# Board.net
KiCad netlist of a schematic drawn in EAGLE
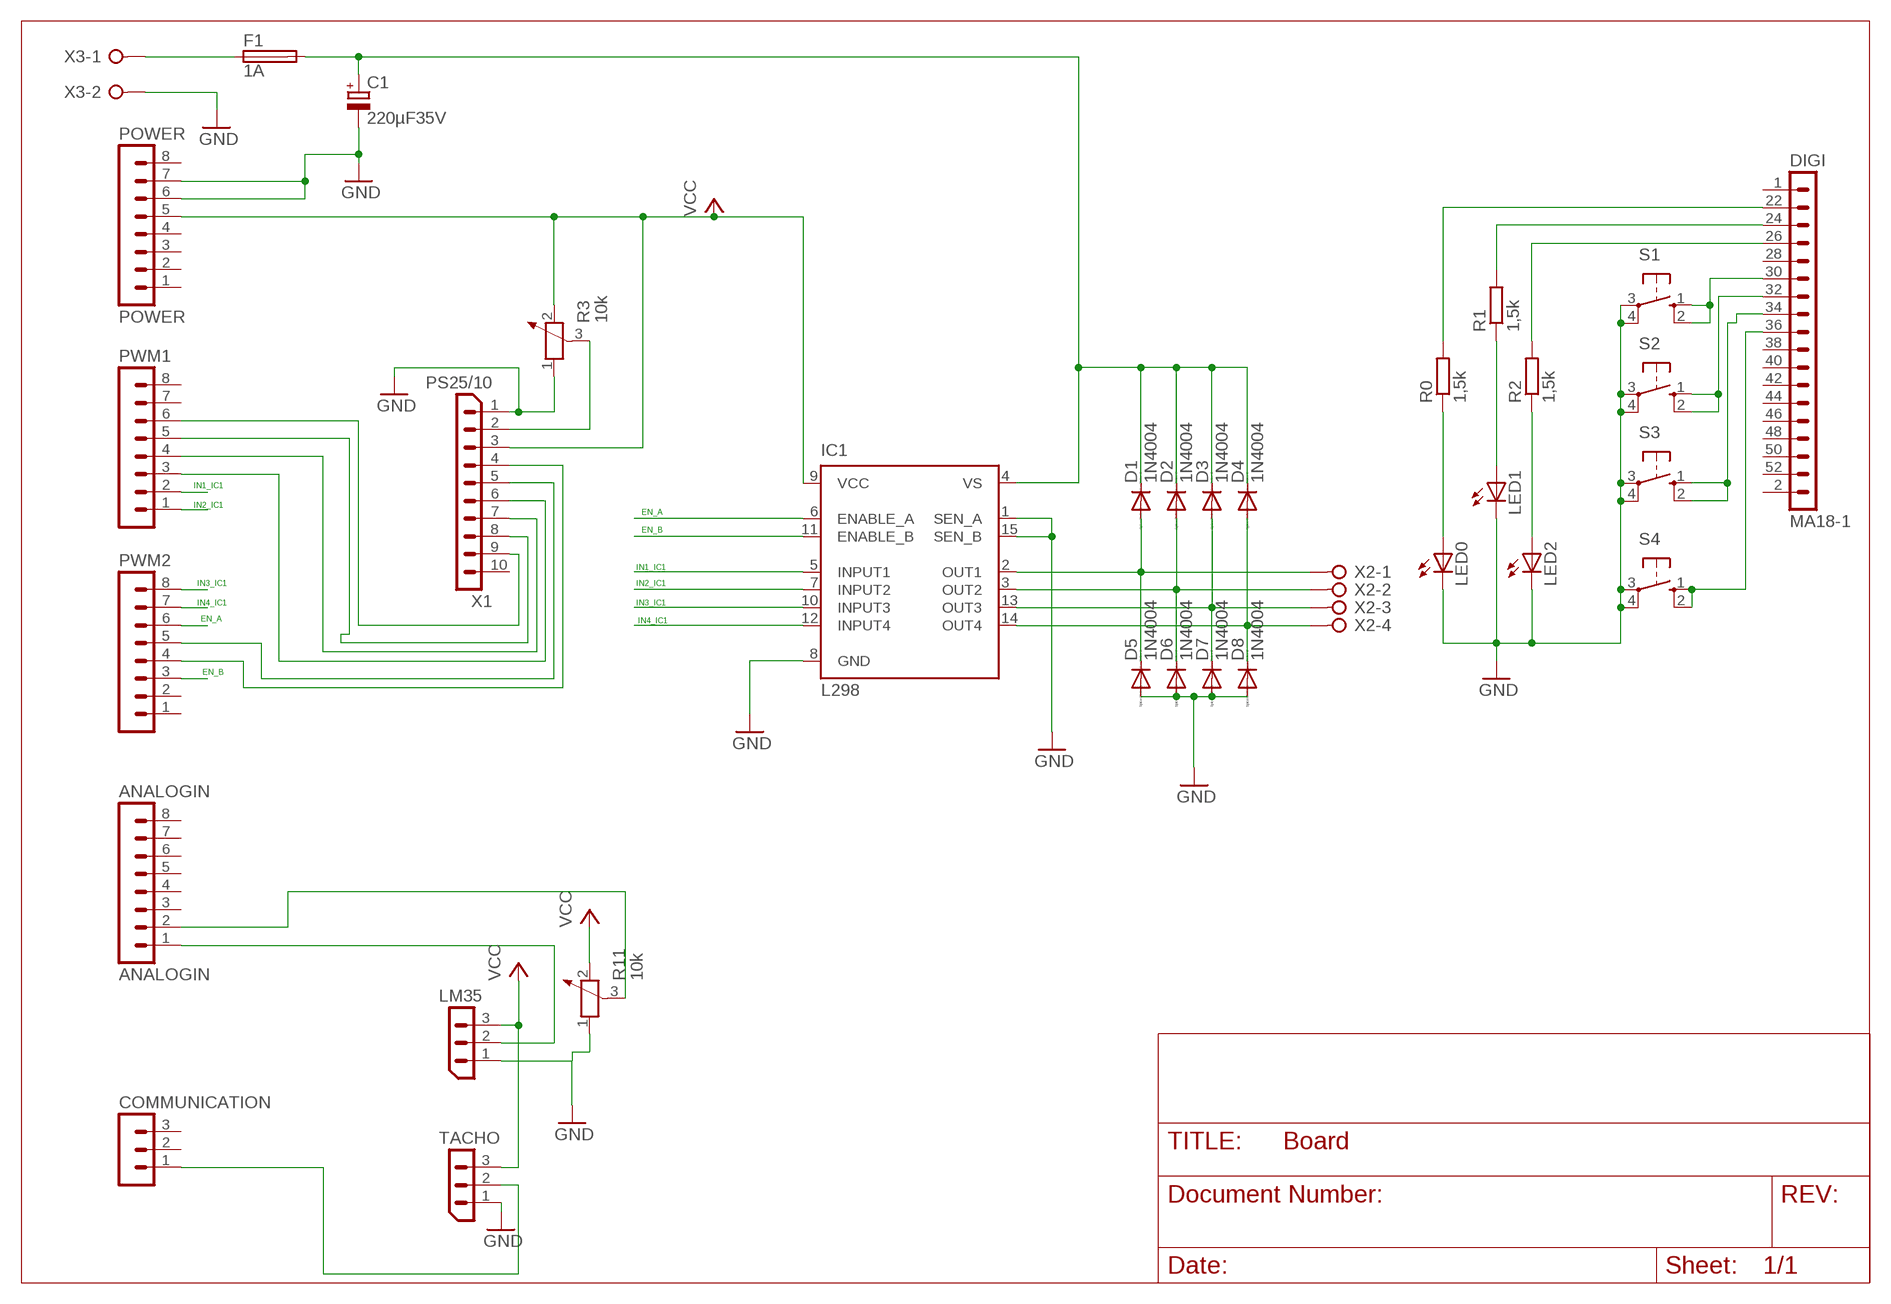
[diagram p0: schematic, sheet 1]

(export (version "E")
  (design (tool "Eeschema 10.0.6"))
  (components
    (comp (ref "ANALOGIN")
      (value "ANALOGIN")
      (footprint "eagle-import:MA08-1")
      (libsource (lib "eagle-import") (part "MA08-1"))
    )
    (comp (ref "C1")
      (value "220µF35V")
      (footprint "eagle-import:E5-10,5")
      (libsource (lib "eagle-import") (part "CPOL-EUE5-10.5"))
    )
    (comp (ref "COMMUNICATION")
      (value "MA03-1")
      (footprint "eagle-import:MA03-1")
      (libsource (lib "eagle-import") (part "MA03-1"))
    )
    (comp (ref "D1")
      (value "1N4004")
      (footprint "eagle-import:DO41-10")
      (libsource (lib "eagle-import") (part "1N4004"))
    )
    (comp (ref "D2")
      (value "1N4004")
      (footprint "eagle-import:DO41-10")
      (libsource (lib "eagle-import") (part "1N4004"))
    )
    (comp (ref "D3")
      (value "1N4004")
      (footprint "eagle-import:DO41-10")
      (libsource (lib "eagle-import") (part "1N4004"))
    )
    (comp (ref "D4")
      (value "1N4004")
      (footprint "eagle-import:DO41-10")
      (libsource (lib "eagle-import") (part "1N4004"))
    )
    (comp (ref "D5")
      (value "1N4004")
      (footprint "eagle-import:DO41-10")
      (libsource (lib "eagle-import") (part "1N4004"))
    )
    (comp (ref "D6")
      (value "1N4004")
      (footprint "eagle-import:DO41-10")
      (libsource (lib "eagle-import") (part "1N4004"))
    )
    (comp (ref "D7")
      (value "1N4004")
      (footprint "eagle-import:DO41-10")
      (libsource (lib "eagle-import") (part "1N4004"))
    )
    (comp (ref "D8")
      (value "1N4004")
      (footprint "eagle-import:DO41-10")
      (libsource (lib "eagle-import") (part "1N4004"))
    )
    (comp (ref "DIGI")
      (value "MA18-1")
      (footprint "eagle-import:MA18-1")
      (libsource (lib "eagle-import") (part "MA18-1"))
    )
    (comp (ref "F1")
      (value "1A")
      (footprint "eagle-import:19560")
      (fields (field (name "MPN") "56000001009"))
      (libsource (lib "eagle-import") (part "19560"))
    )
    (comp (ref "IC1")
      (value "L298")
      (footprint "eagle-import:MULTIWATT-15")
      (fields (field (name "MPN") "L298N"))
      (libsource (lib "eagle-import") (part "L298"))
    )
    (comp (ref "LED0")
      (value "LED3MM")
      (footprint "eagle-import:LED3MM")
      (libsource (lib "eagle-import") (part "LED3MM"))
    )
    (comp (ref "LED1")
      (value "LED3MM")
      (footprint "eagle-import:LED3MM")
      (libsource (lib "eagle-import") (part "LED3MM"))
    )
    (comp (ref "LED2")
      (value "LED3MM")
      (footprint "eagle-import:LED3MM")
      (libsource (lib "eagle-import") (part "LED3MM"))
    )
    (comp (ref "LM35")
      (value "PS25/10")
      (footprint "eagle-import:PS25_10")
      (libsource (lib "eagle-import") (part "Platinenstecker_3pol_PS25/10"))
    )
    (comp (ref "POWER")
      (value "POWER")
      (footprint "eagle-import:MA08-1")
      (libsource (lib "eagle-import") (part "MA08-1"))
    )
    (comp (ref "PWM1")
      (value "MA08-1")
      (footprint "eagle-import:MA08-1")
      (libsource (lib "eagle-import") (part "MA08-1"))
    )
    (comp (ref "PWM2")
      (value "MA08-1")
      (footprint "eagle-import:MA08-1")
      (libsource (lib "eagle-import") (part "MA08-1"))
    )
    (comp (ref "R0")
      (value "1,5k")
      (footprint "eagle-import:0207_10")
      (libsource (lib "eagle-import") (part "R-EU_0207/10"))
    )
    (comp (ref "R1")
      (value "1,5k")
      (footprint "eagle-import:0207_10")
      (libsource (lib "eagle-import") (part "R-EU_0207/10"))
    )
    (comp (ref "R2")
      (value "1,5k")
      (footprint "eagle-import:0207_10")
      (libsource (lib "eagle-import") (part "R-EU_0207/10"))
    )
    (comp (ref "R3")
      (value "10k")
      (footprint "eagle-import:PT-10")
      (libsource (lib "eagle-import") (part "POTENTIOMETER_PT-10"))
    )
    (comp (ref "R11")
      (value "10k")
      (footprint "eagle-import:PT-10")
      (libsource (lib "eagle-import") (part "POTENTIOMETER_PT-10"))
    )
    (comp (ref "S1")
      (value "10-XX")
      (footprint "eagle-import:B3F-10XX")
      (fields (field (name "MPN") "B3F-1000"))
      (libsource (lib "eagle-import") (part "10-XX"))
    )
    (comp (ref "S2")
      (value "10-XX")
      (footprint "eagle-import:B3F-10XX")
      (fields (field (name "MPN") "B3F-1000"))
      (libsource (lib "eagle-import") (part "10-XX"))
    )
    (comp (ref "S3")
      (value "10-XX")
      (footprint "eagle-import:B3F-10XX")
      (fields (field (name "MPN") "B3F-1000"))
      (libsource (lib "eagle-import") (part "10-XX"))
    )
    (comp (ref "S4")
      (value "10-XX")
      (footprint "eagle-import:B3F-10XX")
      (fields (field (name "MPN") "B3F-1000"))
      (libsource (lib "eagle-import") (part "10-XX"))
    )
    (comp (ref "TACHO")
      (value "PS25/10")
      (footprint "eagle-import:PS25_10")
      (libsource (lib "eagle-import") (part "Platinenstecker_3pol_PS25/10"))
    )
    (comp (ref "X1")
      (value "PS25/10")
      (footprint "eagle-import:PS25_10")
      (libsource (lib "eagle-import") (part "PS25/10"))
    )
    (comp (ref "X2")
      (value "W237-04P")
      (footprint "eagle-import:W237-4P")
      (libsource (lib "eagle-import") (part "W237-04P"))
    )
    (comp (ref "X3")
      (value "W237-02P")
      (footprint "eagle-import:W237-132")
      (libsource (lib "eagle-import") (part "W237-02P"))
    )
  )
  (nets
    (net (code "1") (name "/EN_A") (class "Default")
      (node (ref "IC1") (pin "6") (pinfunction "ENABLE_A_6") (pintype "input"))
      (node (ref "PWM2") (pin "6") (pinfunction "6_6") (pintype "passive"))
    )
    (net (code "2") (name "/EN_B") (class "Default")
      (node (ref "IC1") (pin "11") (pinfunction "ENABLE_B_11") (pintype "input"))
      (node (ref "PWM2") (pin "3") (pinfunction "3_3") (pintype "passive"))
    )
    (net (code "3") (name "/IN1_IC1") (class "Default")
      (node (ref "IC1") (pin "5") (pinfunction "INPUT1_5") (pintype "input"))
      (node (ref "PWM1") (pin "2") (pinfunction "2_2") (pintype "passive"))
    )
    (net (code "4") (name "/IN2_IC1") (class "Default")
      (node (ref "IC1") (pin "7") (pinfunction "INPUT2_7") (pintype "input"))
      (node (ref "PWM1") (pin "1") (pinfunction "1_1") (pintype "passive"))
    )
    (net (code "5") (name "/IN3_IC1") (class "Default")
      (node (ref "IC1") (pin "10") (pinfunction "INPUT3_10") (pintype "input"))
      (node (ref "PWM2") (pin "8") (pinfunction "8_8") (pintype "passive"))
    )
    (net (code "6") (name "/IN4_IC1") (class "Default")
      (node (ref "IC1") (pin "12") (pinfunction "INPUT4_12") (pintype "input"))
      (node (ref "PWM2") (pin "7") (pinfunction "7_7") (pintype "passive"))
    )
    (net (code "7") (name "GND") (class "Default")
      (node (ref "C1") (pin "-") (pinfunction "-_-") (pintype "passive"))
      (node (ref "D5") (pin "A") (pinfunction "A_A") (pintype "passive"))
      (node (ref "D6") (pin "A") (pinfunction "A_A") (pintype "passive"))
      (node (ref "D7") (pin "A") (pinfunction "A_A") (pintype "passive"))
      (node (ref "D8") (pin "A") (pinfunction "A_A") (pintype "passive"))
      (node (ref "IC1") (pin "1") (pinfunction "SEN_A_1") (pintype "input"))
      (node (ref "IC1") (pin "15") (pinfunction "SEN_B_15") (pintype "input"))
      (node (ref "IC1") (pin "8") (pinfunction "GND_8") (pintype "power_in"))
      (node (ref "LED0") (pin "K") (pinfunction "C_K") (pintype "passive"))
      (node (ref "LED1") (pin "K") (pinfunction "C_K") (pintype "passive"))
      (node (ref "LED2") (pin "K") (pinfunction "C_K") (pintype "passive"))
      (node (ref "LM35") (pin "1") (pinfunction "1_1") (pintype "passive"))
      (node (ref "POWER") (pin "6") (pinfunction "6_6") (pintype "passive"))
      (node (ref "POWER") (pin "7") (pinfunction "7_7") (pintype "passive"))
      (node (ref "R11") (pin "1") (pinfunction "1_1") (pintype "passive"))
      (node (ref "R3") (pin "1") (pinfunction "1_1") (pintype "passive"))
      (node (ref "S1") (pin "3") (pinfunction "P_3") (pintype "passive"))
      (node (ref "S1") (pin "4") (pinfunction "P1_4") (pintype "passive"))
      (node (ref "S2") (pin "3") (pinfunction "P_3") (pintype "passive"))
      (node (ref "S2") (pin "4") (pinfunction "P1_4") (pintype "passive"))
      (node (ref "S3") (pin "3") (pinfunction "P_3") (pintype "passive"))
      (node (ref "S3") (pin "4") (pinfunction "P1_4") (pintype "passive"))
      (node (ref "S4") (pin "3") (pinfunction "P_3") (pintype "passive"))
      (node (ref "S4") (pin "4") (pinfunction "P1_4") (pintype "passive"))
      (node (ref "TACHO") (pin "1") (pinfunction "1_1") (pintype "passive"))
      (node (ref "X1") (pin "1") (pinfunction "1_1") (pintype "passive"))
      (node (ref "X3") (pin "2") (pinfunction "KL_2") (pintype "passive"))
    )
    (net (code "8") (name "Net-(ANALOGIN-Pad1)") (class "Default")
      (node (ref "ANALOGIN") (pin "1") (pinfunction "1_1") (pintype "passive"))
      (node (ref "LM35") (pin "2") (pinfunction "2_2") (pintype "passive"))
    )
    (net (code "9") (name "Net-(ANALOGIN-Pad2)") (class "Default")
      (node (ref "ANALOGIN") (pin "2") (pinfunction "2_2") (pintype "passive"))
      (node (ref "R11") (pin "3") (pinfunction "3_3") (pintype "passive"))
    )
    (net (code "10") (name "Net-(COMMUNICATION-Pad1)") (class "Default")
      (node (ref "COMMUNICATION") (pin "1") (pinfunction "1_1") (pintype "passive"))
      (node (ref "TACHO") (pin "2") (pinfunction "2_2") (pintype "passive"))
    )
    (net (code "11") (name "Net-(DIGI-Pad22)") (class "Default")
      (node (ref "DIGI") (pin "22") (pinfunction "22_22") (pintype "passive"))
      (node (ref "R0") (pin "2") (pinfunction "2_2") (pintype "passive"))
    )
    (net (code "12") (name "Net-(DIGI-Pad24)") (class "Default")
      (node (ref "DIGI") (pin "24") (pinfunction "24_24") (pintype "passive"))
      (node (ref "R1") (pin "2") (pinfunction "2_2") (pintype "passive"))
    )
    (net (code "13") (name "Net-(DIGI-Pad26)") (class "Default")
      (node (ref "DIGI") (pin "26") (pinfunction "26_26") (pintype "passive"))
      (node (ref "R2") (pin "2") (pinfunction "2_2") (pintype "passive"))
    )
    (net (code "14") (name "Net-(IC1-OUT1)") (class "Default")
      (node (ref "D1") (pin "A") (pinfunction "A_A") (pintype "passive"))
      (node (ref "D5") (pin "C") (pinfunction "C_C") (pintype "passive"))
      (node (ref "IC1") (pin "2") (pinfunction "OUT1_2") (pintype "output"))
      (node (ref "X2") (pin "1") (pinfunction "KL_1") (pintype "passive"))
    )
    (net (code "15") (name "Net-(IC1-OUT2)") (class "Default")
      (node (ref "D2") (pin "A") (pinfunction "A_A") (pintype "passive"))
      (node (ref "D6") (pin "C") (pinfunction "C_C") (pintype "passive"))
      (node (ref "IC1") (pin "3") (pinfunction "OUT2_3") (pintype "output"))
      (node (ref "X2") (pin "2") (pinfunction "KL_2") (pintype "passive"))
    )
    (net (code "16") (name "Net-(IC1-OUT3)") (class "Default")
      (node (ref "D3") (pin "A") (pinfunction "A_A") (pintype "passive"))
      (node (ref "D7") (pin "C") (pinfunction "C_C") (pintype "passive"))
      (node (ref "IC1") (pin "13") (pinfunction "OUT3_13") (pintype "output"))
      (node (ref "X2") (pin "3") (pinfunction "KL_3") (pintype "passive"))
    )
    (net (code "17") (name "Net-(IC1-OUT4)") (class "Default")
      (node (ref "D4") (pin "A") (pinfunction "A_A") (pintype "passive"))
      (node (ref "D8") (pin "C") (pinfunction "C_C") (pintype "passive"))
      (node (ref "IC1") (pin "14") (pinfunction "OUT4_14") (pintype "output"))
      (node (ref "X2") (pin "4") (pinfunction "KL_4") (pintype "passive"))
    )
    (net (code "18") (name "Net-(IC1-VS)") (class "Default")
      (node (ref "C1") (pin "+") (pinfunction "+_+") (pintype "passive"))
      (node (ref "D1") (pin "C") (pinfunction "C_C") (pintype "passive"))
      (node (ref "D2") (pin "C") (pinfunction "C_C") (pintype "passive"))
      (node (ref "D3") (pin "C") (pinfunction "C_C") (pintype "passive"))
      (node (ref "D4") (pin "C") (pinfunction "C_C") (pintype "passive"))
      (node (ref "F1") (pin "2") (pinfunction "2_2") (pintype "passive"))
      (node (ref "IC1") (pin "4") (pinfunction "VS_4") (pintype "power_in"))
    )
    (net (code "19") (name "Net-(LED0-PadA)") (class "Default")
      (node (ref "LED0") (pin "A") (pinfunction "A_A") (pintype "passive"))
      (node (ref "R0") (pin "1") (pinfunction "1_1") (pintype "passive"))
    )
    (net (code "20") (name "Net-(LED1-PadA)") (class "Default")
      (node (ref "LED1") (pin "A") (pinfunction "A_A") (pintype "passive"))
      (node (ref "R1") (pin "1") (pinfunction "1_1") (pintype "passive"))
    )
    (net (code "21") (name "Net-(LED2-PadA)") (class "Default")
      (node (ref "LED2") (pin "A") (pinfunction "A_A") (pintype "passive"))
      (node (ref "R2") (pin "1") (pinfunction "1_1") (pintype "passive"))
    )
    (net (code "22") (name "Net-(PWM1-Pad3)") (class "Default")
      (node (ref "PWM1") (pin "3") (pinfunction "3_3") (pintype "passive"))
      (node (ref "X1") (pin "6") (pinfunction "6_6") (pintype "passive"))
    )
    (net (code "23") (name "Net-(PWM1-Pad4)") (class "Default")
      (node (ref "PWM1") (pin "4") (pinfunction "4_4") (pintype "passive"))
      (node (ref "X1") (pin "7") (pinfunction "7_7") (pintype "passive"))
    )
    (net (code "24") (name "Net-(PWM1-Pad5)") (class "Default")
      (node (ref "PWM1") (pin "5") (pinfunction "5_5") (pintype "passive"))
      (node (ref "X1") (pin "8") (pinfunction "8_8") (pintype "passive"))
    )
    (net (code "25") (name "Net-(PWM1-Pad6)") (class "Default")
      (node (ref "PWM1") (pin "6") (pinfunction "6_6") (pintype "passive"))
      (node (ref "X1") (pin "9") (pinfunction "9_9") (pintype "passive"))
    )
    (net (code "26") (name "Net-(PWM2-Pad4)") (class "Default")
      (node (ref "PWM2") (pin "4") (pinfunction "4_4") (pintype "passive"))
      (node (ref "X1") (pin "4") (pinfunction "4_4") (pintype "passive"))
    )
    (net (code "27") (name "Net-(PWM2-Pad5)") (class "Default")
      (node (ref "PWM2") (pin "5") (pinfunction "5_5") (pintype "passive"))
      (node (ref "X1") (pin "5") (pinfunction "5_5") (pintype "passive"))
    )
    (net (code "28") (name "Net-(R3-Pad3)") (class "Default")
      (node (ref "R3") (pin "3") (pinfunction "3_3") (pintype "passive"))
      (node (ref "X1") (pin "2") (pinfunction "2_2") (pintype "passive"))
    )
    (net (code "29") (name "Net-(S1-S)") (class "Default")
      (node (ref "DIGI") (pin "30") (pinfunction "30_30") (pintype "passive"))
      (node (ref "S1") (pin "1") (pinfunction "S_1") (pintype "passive"))
      (node (ref "S1") (pin "2") (pinfunction "S1_2") (pintype "passive"))
    )
    (net (code "30") (name "Net-(S2-S)") (class "Default")
      (node (ref "DIGI") (pin "32") (pinfunction "32_32") (pintype "passive"))
      (node (ref "S2") (pin "1") (pinfunction "S_1") (pintype "passive"))
      (node (ref "S2") (pin "2") (pinfunction "S1_2") (pintype "passive"))
    )
    (net (code "31") (name "Net-(S3-S)") (class "Default")
      (node (ref "DIGI") (pin "34") (pinfunction "34_34") (pintype "passive"))
      (node (ref "S3") (pin "1") (pinfunction "S_1") (pintype "passive"))
      (node (ref "S3") (pin "2") (pinfunction "S1_2") (pintype "passive"))
    )
    (net (code "32") (name "Net-(S4-S)") (class "Default")
      (node (ref "DIGI") (pin "36") (pinfunction "36_36") (pintype "passive"))
      (node (ref "S4") (pin "1") (pinfunction "S_1") (pintype "passive"))
      (node (ref "S4") (pin "2") (pinfunction "S1_2") (pintype "passive"))
    )
    (net (code "33") (name "Net-(X3A-KL)") (class "Default")
      (node (ref "F1") (pin "1") (pinfunction "1_1") (pintype "passive"))
      (node (ref "X3") (pin "1") (pinfunction "KL_1") (pintype "passive"))
    )
    (net (code "34") (name "VCC") (class "Default")
      (node (ref "IC1") (pin "9") (pinfunction "VCC_9") (pintype "power_in"))
      (node (ref "LM35") (pin "3") (pinfunction "3_3") (pintype "passive"))
      (node (ref "POWER") (pin "5") (pinfunction "5_5") (pintype "passive"))
      (node (ref "R11") (pin "2") (pinfunction "2_2") (pintype "passive"))
      (node (ref "R3") (pin "2") (pinfunction "2_2") (pintype "passive"))
      (node (ref "TACHO") (pin "3") (pinfunction "3_3") (pintype "passive"))
      (node (ref "X1") (pin "3") (pinfunction "3_3") (pintype "passive"))
    )
    (net (code "35") (name "unconnected-(ANALOGIN-Pad3)") (class "Default")
      (node (ref "ANALOGIN") (pin "3") (pinfunction "3_3") (pintype "passive"))
    )
    (net (code "36") (name "unconnected-(ANALOGIN-Pad4)") (class "Default")
      (node (ref "ANALOGIN") (pin "4") (pinfunction "4_4") (pintype "passive"))
    )
    (net (code "37") (name "unconnected-(ANALOGIN-Pad5)") (class "Default")
      (node (ref "ANALOGIN") (pin "5") (pinfunction "5_5") (pintype "passive"))
    )
    (net (code "38") (name "unconnected-(ANALOGIN-Pad6)") (class "Default")
      (node (ref "ANALOGIN") (pin "6") (pinfunction "6_6") (pintype "passive"))
    )
    (net (code "39") (name "unconnected-(ANALOGIN-Pad7)") (class "Default")
      (node (ref "ANALOGIN") (pin "7") (pinfunction "7_7") (pintype "passive"))
    )
    (net (code "40") (name "unconnected-(ANALOGIN-Pad8)") (class "Default")
      (node (ref "ANALOGIN") (pin "8") (pinfunction "8_8") (pintype "passive"))
    )
    (net (code "41") (name "unconnected-(COMMUNICATION-Pad2)") (class "Default")
      (node (ref "COMMUNICATION") (pin "2") (pinfunction "2_2") (pintype "passive"))
    )
    (net (code "42") (name "unconnected-(COMMUNICATION-Pad3)") (class "Default")
      (node (ref "COMMUNICATION") (pin "3") (pinfunction "3_3") (pintype "passive"))
    )
    (net (code "43") (name "unconnected-(DIGI-Pad1)") (class "Default")
      (node (ref "DIGI") (pin "1") (pinfunction "1_1") (pintype "passive"))
    )
    (net (code "44") (name "unconnected-(DIGI-Pad2)") (class "Default")
      (node (ref "DIGI") (pin "2") (pinfunction "2_2") (pintype "passive"))
    )
    (net (code "45") (name "unconnected-(DIGI-Pad28)") (class "Default")
      (node (ref "DIGI") (pin "28") (pinfunction "28_28") (pintype "passive"))
    )
    (net (code "46") (name "unconnected-(DIGI-Pad38)") (class "Default")
      (node (ref "DIGI") (pin "38") (pinfunction "38_38") (pintype "passive"))
    )
    (net (code "47") (name "unconnected-(DIGI-Pad40)") (class "Default")
      (node (ref "DIGI") (pin "40") (pinfunction "40_40") (pintype "passive"))
    )
    (net (code "48") (name "unconnected-(DIGI-Pad42)") (class "Default")
      (node (ref "DIGI") (pin "42") (pinfunction "42_42") (pintype "passive"))
    )
    (net (code "49") (name "unconnected-(DIGI-Pad44)") (class "Default")
      (node (ref "DIGI") (pin "44") (pinfunction "44_44") (pintype "passive"))
    )
    (net (code "50") (name "unconnected-(DIGI-Pad46)") (class "Default")
      (node (ref "DIGI") (pin "46") (pinfunction "46_46") (pintype "passive"))
    )
    (net (code "51") (name "unconnected-(DIGI-Pad48)") (class "Default")
      (node (ref "DIGI") (pin "48") (pinfunction "48_48") (pintype "passive"))
    )
    (net (code "52") (name "unconnected-(DIGI-Pad50)") (class "Default")
      (node (ref "DIGI") (pin "50") (pinfunction "50_50") (pintype "passive"))
    )
    (net (code "53") (name "unconnected-(DIGI-Pad52)") (class "Default")
      (node (ref "DIGI") (pin "52") (pinfunction "52_52") (pintype "passive"))
    )
    (net (code "54") (name "unconnected-(POWER-Pad1)") (class "Default")
      (node (ref "POWER") (pin "1") (pinfunction "1_1") (pintype "passive"))
    )
    (net (code "55") (name "unconnected-(POWER-Pad2)") (class "Default")
      (node (ref "POWER") (pin "2") (pinfunction "2_2") (pintype "passive"))
    )
    (net (code "56") (name "unconnected-(POWER-Pad3)") (class "Default")
      (node (ref "POWER") (pin "3") (pinfunction "3_3") (pintype "passive"))
    )
    (net (code "57") (name "unconnected-(POWER-Pad4)") (class "Default")
      (node (ref "POWER") (pin "4") (pinfunction "4_4") (pintype "passive"))
    )
    (net (code "58") (name "unconnected-(POWER-Pad8)") (class "Default")
      (node (ref "POWER") (pin "8") (pinfunction "8_8") (pintype "passive"))
    )
    (net (code "59") (name "unconnected-(PWM1-Pad7)") (class "Default")
      (node (ref "PWM1") (pin "7") (pinfunction "7_7") (pintype "passive"))
    )
    (net (code "60") (name "unconnected-(PWM1-Pad8)") (class "Default")
      (node (ref "PWM1") (pin "8") (pinfunction "8_8") (pintype "passive"))
    )
    (net (code "61") (name "unconnected-(PWM2-Pad1)") (class "Default")
      (node (ref "PWM2") (pin "1") (pinfunction "1_1") (pintype "passive"))
    )
    (net (code "62") (name "unconnected-(PWM2-Pad2)") (class "Default")
      (node (ref "PWM2") (pin "2") (pinfunction "2_2") (pintype "passive"))
    )
    (net (code "63") (name "unconnected-(X1-Pad10)") (class "Default")
      (node (ref "X1") (pin "10") (pinfunction "10_10") (pintype "passive"))
    )
  )
)
